# H01R01.net
KiCad netlist of a schematic drawn in EAGLE
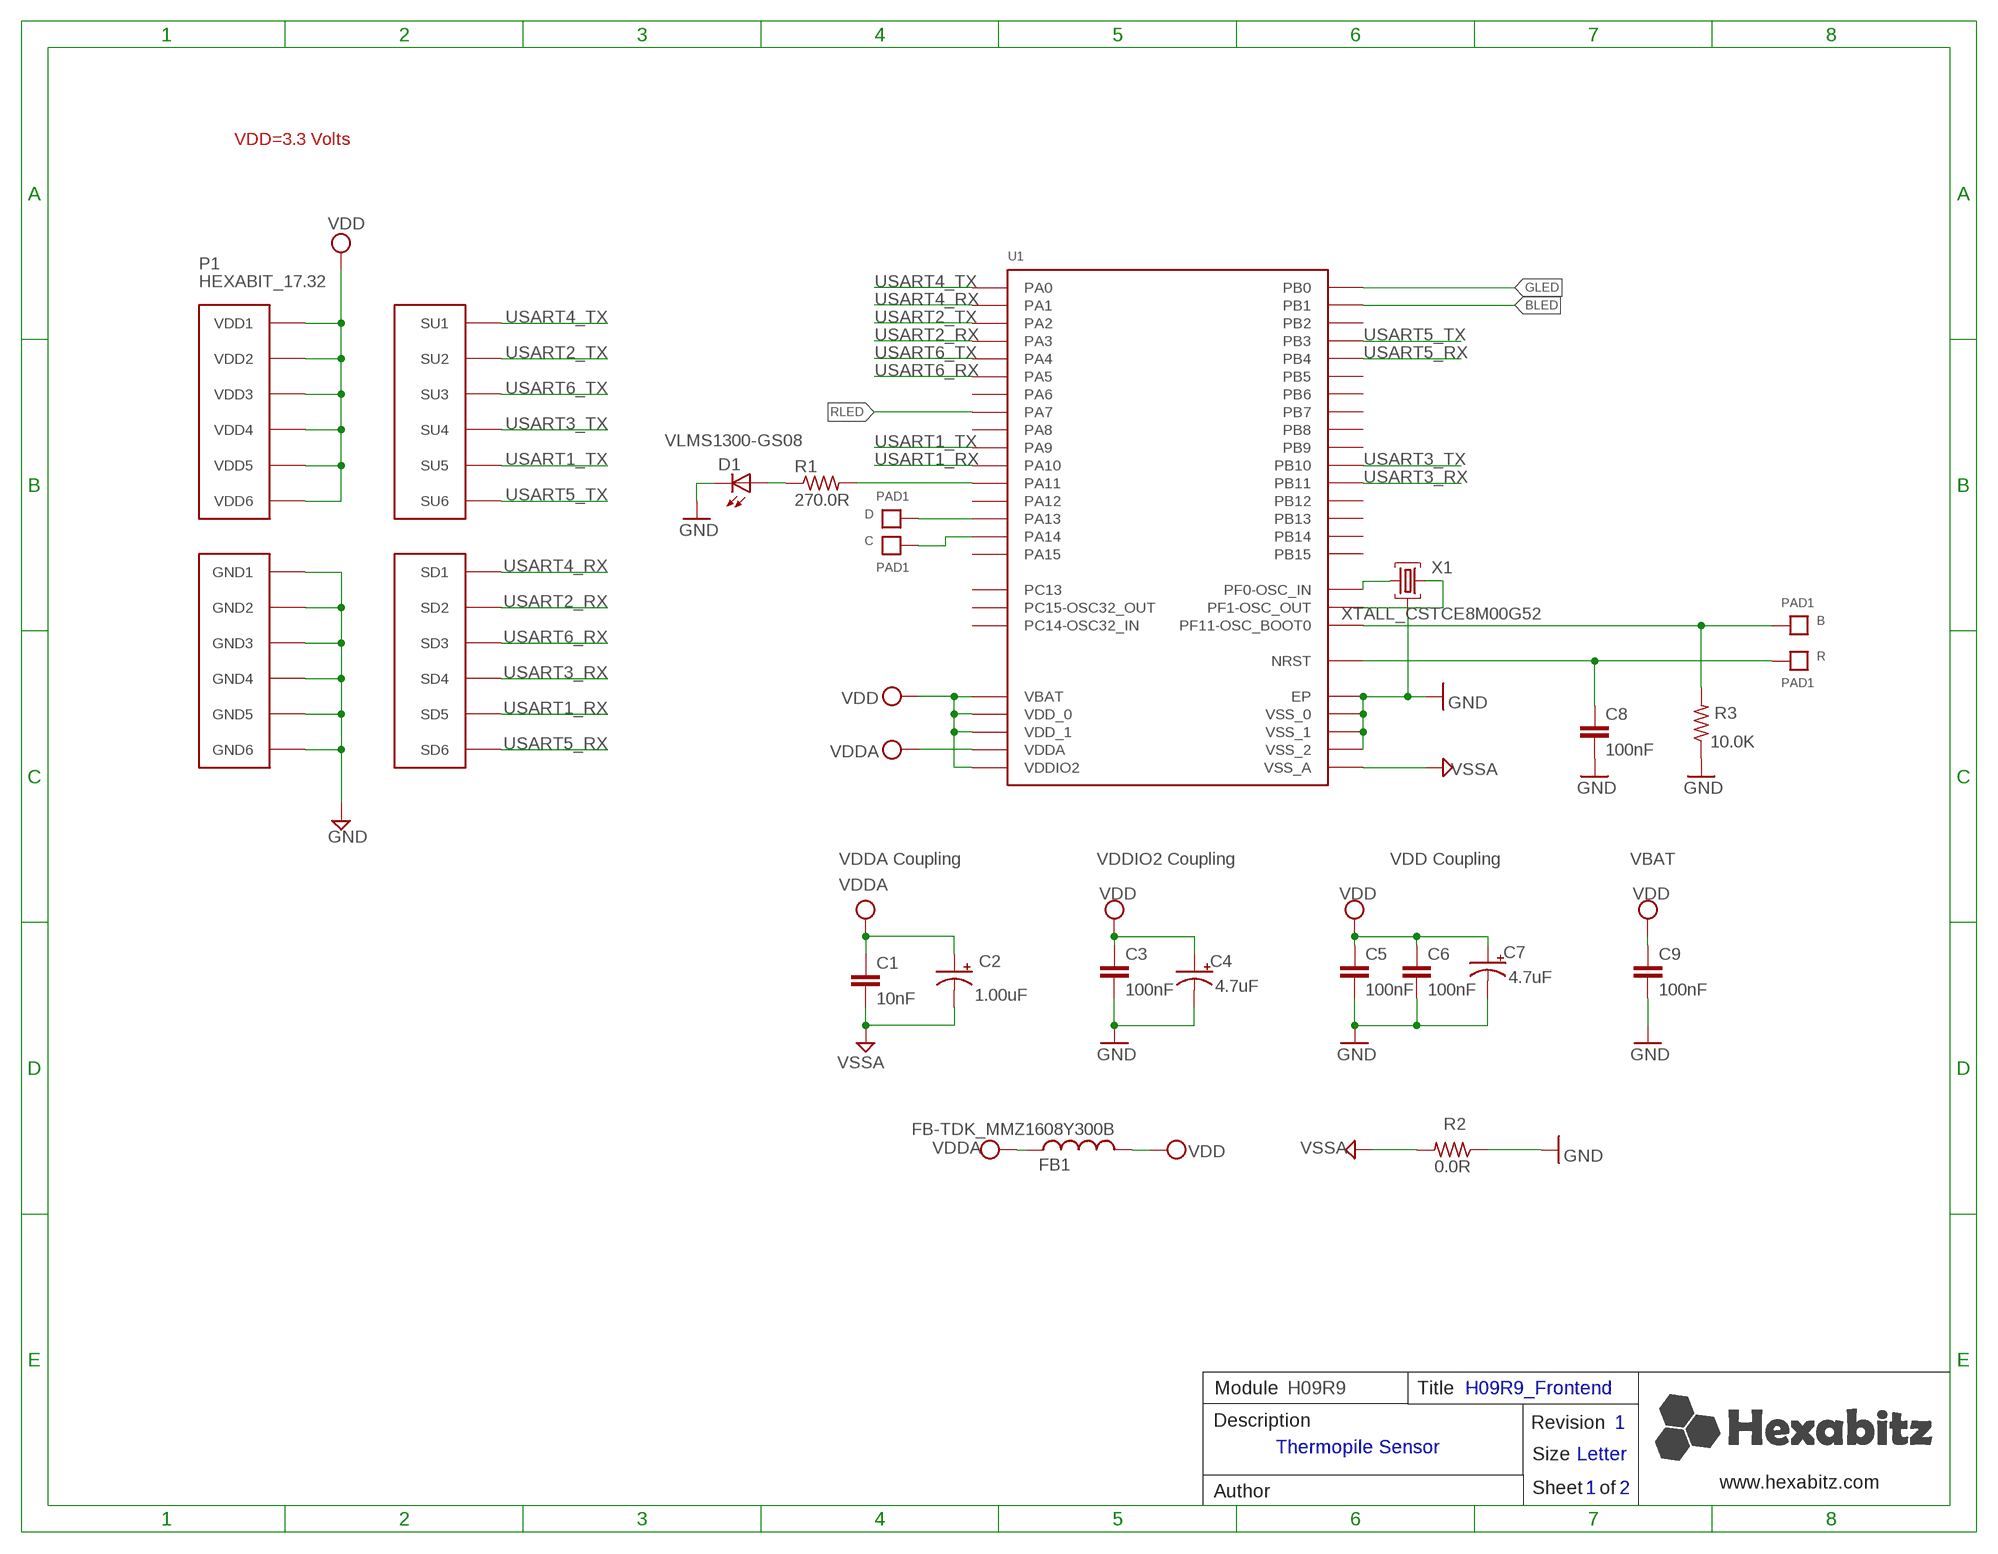
[diagram p0: schematic, sheet 1]
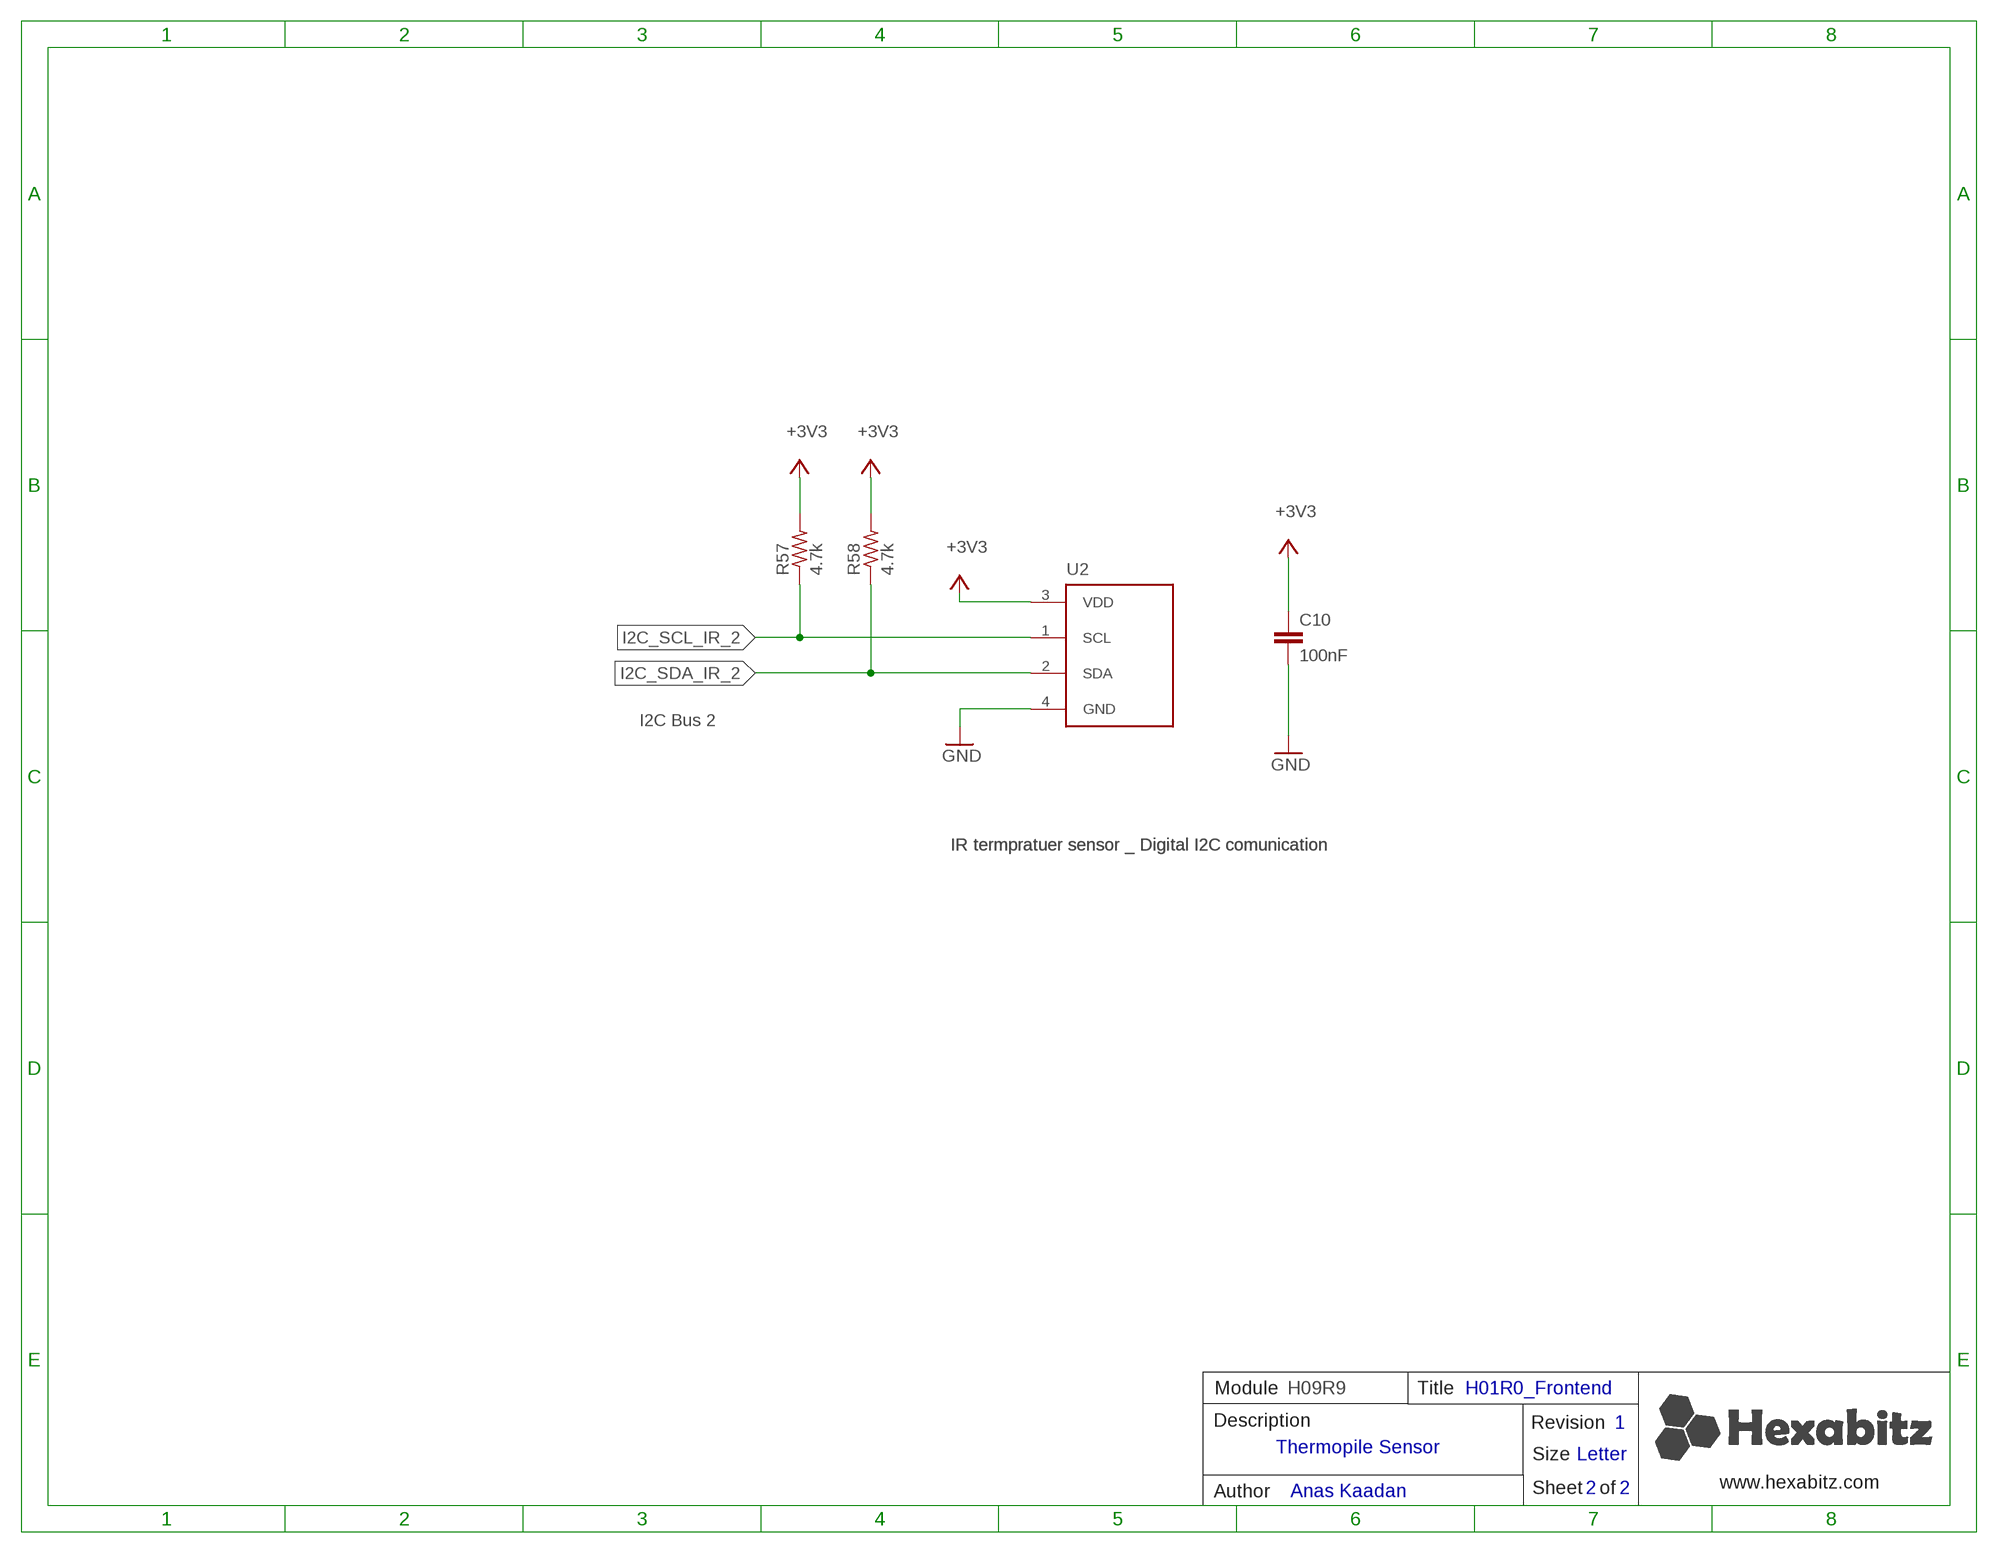
[diagram p1: schematic, sheet 2]

(export (version "E")
  (design (tool "Eeschema 10.0.6"))
  (components
    (comp (ref "C10")
      (value "100nF")
      (footprint "eagle-import:C-0603")
      (fields
        (field (name "CAPACITANCE") "100nF")
        (field (name "MFN") "KEMET")
        (field (name "MPN") "C0603C104K8RACTU")
        (field (name "OCTOPART_URL") "https://octopart.com/c0603c104k8ractu-kemet-145075?r=sp&s=9bS9ASSwSEqMCE9KBEQZ0g")
        (field (name "TOLERANCE") "10%")
        (field (name "VOLTAGE_RATING") "10V")
      )
      (libsource (lib "eagle-import") (part "C-0603"))
    )
    (comp (ref "R57")
      (value "4.7k")
      (footprint "eagle-import:R-0603")
      (fields
        (field (name "MFN") "Yageo")
        (field (name "MPN") "RC0603FR-07270RL")
        (field (name "OCTOPART_URL") "https://octopart.com/crcw06032k20fkea-vishay-40018987")
        (field (name "TOLERANCE") "±1%")
      )
      (libsource (lib "eagle-import") (part "R-0603"))
    )
    (comp (ref "R58")
      (value "4.7k")
      (footprint "eagle-import:R-0603")
      (fields
        (field (name "MFN") "Yageo")
        (field (name "MPN") "RC0603FR-07270RL")
        (field (name "OCTOPART_URL") "https://octopart.com/crcw06032k20fkea-vishay-40018987")
        (field (name "TOLERANCE") "±1%")
      )
      (libsource (lib "eagle-import") (part "R-0603"))
    )
    (comp (ref "U2")
      (value "TSD305-1C55")
      (footprint "eagle-import:TEMPERATURESENSOR-TO5")
      (fields (field (name "MPN") "G-TPMO-101"))
      (libsource (lib "eagle-import") (part "TSD305-1C55"))
    )
    (comp (ref "B")
      (value "PAD1")
      (footprint "eagle-import:PAD1")
      (libsource (lib "eagle-import") (part "PAD1"))
    )
    (comp (ref "C")
      (value "PAD1")
      (footprint "eagle-import:PAD1")
      (libsource (lib "eagle-import") (part "PAD1"))
    )
    (comp (ref "C1")
      (value "10nF")
      (footprint "eagle-import:C-0603")
      (fields
        (field (name "CAPACITANCE") "10nF")
        (field (name "MFN") "KEMET")
        (field (name "MPN") "C0603C103K5RACTU")
        (field (name "OCTOPART_URL") "https://octopart.com/c0603c103k5ractu-kemet-133094?r=sp&s=R_iPBxLnSmGqhkU2rIMFpg")
        (field (name "TOLERANCE") "10%")
        (field (name "VOLTAGE_RATING") "50V")
      )
      (libsource (lib "eagle-import") (part "Hexabitz_C-0603"))
    )
    (comp (ref "C2")
      (value "1.00uF")
      (footprint "eagle-import:C-0805-POL")
      (fields
        (field (name "CAPACITANCE") "1.00uF")
        (field (name "MFN") "Yageo")
        (field (name "MPN") "CC0805KKX7R7BB105")
        (field (name "OCTOPART_URL") "https://octopart.com/cc0805kkx7r7bb105-yageo-8376555?r=sp&s=YKl1wwtkROau_X5nniH2ig")
        (field (name "TOLERANCE") "10%")
        (field (name "VOLTAGE_RATING") "16V")
      )
      (libsource (lib "eagle-import") (part "C-0805-POL"))
    )
    (comp (ref "C3")
      (value "100nF")
      (footprint "eagle-import:C-0603")
      (fields
        (field (name "CAPACITANCE") "100nF")
        (field (name "MFN") "KEMET")
        (field (name "MPN") "C0603C104K8RACTU")
        (field (name "OCTOPART_URL") "https://octopart.com/c0603c104k8ractu-kemet-145075?r=sp&s=9bS9ASSwSEqMCE9KBEQZ0g")
        (field (name "TOLERANCE") "10%")
        (field (name "VOLTAGE_RATING") "10V")
      )
      (libsource (lib "eagle-import") (part "Hexabitz_C-0603"))
    )
    (comp (ref "C4")
      (value "4.7uF")
      (footprint "eagle-import:C-0805-POL")
      (fields
        (field (name "CAPACITANCE") "4.7uF")
        (field (name "MFN") "Murata")
        (field (name "MPN") "GRM21BC81E475KA12L")
        (field (name "OCTOPART_URL") "https://octopart.com/grm21bc81e475ka12l-murata-10331911?r=sp&s=RY3qZSD8T6mG6TC9CHI5qQ")
        (field (name "TOLERANCE") "10%")
        (field (name "VOLTAGE_RATING") "25V")
      )
      (libsource (lib "eagle-import") (part "C-0805-POL"))
    )
    (comp (ref "C5")
      (value "100nF")
      (footprint "eagle-import:C-0603")
      (fields
        (field (name "CAPACITANCE") "100nF")
        (field (name "MFN") "KEMET")
        (field (name "MPN") "C0603C104K8RACTU")
        (field (name "OCTOPART_URL") "https://octopart.com/c0603c104k8ractu-kemet-145075?r=sp&s=9bS9ASSwSEqMCE9KBEQZ0g")
        (field (name "TOLERANCE") "10%")
        (field (name "VOLTAGE_RATING") "10")
      )
      (libsource (lib "eagle-import") (part "Hexabitz_C-0603"))
    )
    (comp (ref "C6")
      (value "100nF")
      (footprint "eagle-import:C-0603")
      (fields
        (field (name "CAPACITANCE") "100nF")
        (field (name "MFN") "KEMET")
        (field (name "MPN") "C0603C104K8RACTU")
        (field (name "OCTOPART_URL") "https://octopart.com/c0603c104k8ractu-kemet-145075?r=sp&s=9bS9ASSwSEqMCE9KBEQZ0g")
        (field (name "TOLERANCE") "10%")
        (field (name "VOLTAGE_RATING") "10V")
      )
      (libsource (lib "eagle-import") (part "Hexabitz_C-0603"))
    )
    (comp (ref "C7")
      (value "4.7uF")
      (footprint "eagle-import:C-0805-POL")
      (fields
        (field (name "CAPACITANCE") "4.7uF")
        (field (name "MFN") "Murata")
        (field (name "MPN") "GRM21BC81E475KA12L")
        (field (name "OCTOPART_URL") "https://octopart.com/grm21bc81e475ka12l-murata-10331911?r=sp&s=RY3qZSD8T6mG6TC9CHI5qQ")
        (field (name "TOLERANCE") "10%")
        (field (name "VOLTAGE_RATING") "25V")
      )
      (libsource (lib "eagle-import") (part "C-0805-POL"))
    )
    (comp (ref "C8")
      (value "100nF")
      (footprint "eagle-import:C-0603")
      (fields
        (field (name "CAPACITANCE") "100nF")
        (field (name "MFN") "KEMET")
        (field (name "MPN") "C0603C104K8RACTU")
        (field (name "OCTOPART_URL") "https://octopart.com/c0603c104k8ractu-kemet-145075?r=sp&s=9bS9ASSwSEqMCE9KBEQZ0g")
        (field (name "TOLERANCE") "10%")
        (field (name "VOLTAGE_RATING") "10V")
      )
      (libsource (lib "eagle-import") (part "Hexabitz_C-0603"))
    )
    (comp (ref "C9")
      (value "100nF")
      (footprint "eagle-import:C-0603")
      (fields
        (field (name "CAPACITANCE") "100nF")
        (field (name "MFN") "KEMET")
        (field (name "MPN") "C0603C104K8RACTU")
        (field (name "OCTOPART_URL") "https://octopart.com/c0603c104k8ractu-kemet-145075?r=sp&s=9bS9ASSwSEqMCE9KBEQZ0g")
        (field (name "TOLERANCE") "10V")
        (field (name "VOLTAGE_RATING") "10%")
      )
      (libsource (lib "eagle-import") (part "Hexabitz_C-0603"))
    )
    (comp (ref "D")
      (value "PAD1")
      (footprint "eagle-import:PAD1")
      (libsource (lib "eagle-import") (part "PAD1"))
    )
    (comp (ref "D1")
      (value "VLMS1300-GS08")
      (footprint "eagle-import:VLMS1300-GS08")
      (fields
        (field (name "MFN") "Vishay")
        (field (name "MPN") "VLMS1300-GS08")
        (field (name "OCTOPART_URL") "https://octopart.com/vlms1300-gs08-vishay-21709201?r=sp&s=_gcP4_q8T1SC6PJQPTQ9yA")
      )
      (libsource (lib "eagle-import") (part "VLMS1300-GS08"))
    )
    (comp (ref "FB1")
      (value "FB-TDK_MMZ1608Y300B")
      (footprint "eagle-import:FB-TDK_MMZ1608Y300B")
      (fields
        (field (name "MFN") "TDK ")
        (field (name "MPN") "MMZ1608Y300B")
        (field (name "OCTOPART_URL") "https://octopart.com/mmz1608y300b-tdk-368280?r=sp&s=cd9_2ZEqQ9q9UNBuQgHAiA")
      )
      (libsource (lib "eagle-import") (part "FB-TDK_MMZ1608Y300B"))
    )
    (comp (ref "P1")
      (value "HEXABIT_17.32")
      (footprint "eagle-import:HEXABIT_17.32")
      (libsource (lib "eagle-import") (part "HEXABIT_?17.32"))
    )
    (comp (ref "R")
      (value "PAD1")
      (footprint "eagle-import:PAD1")
      (libsource (lib "eagle-import") (part "PAD1"))
    )
    (comp (ref "R1")
      (value "270.0R")
      (footprint "eagle-import:R-0603")
      (fields
        (field (name "MFN") "Yageo")
        (field (name "MPN") "RC0603FR-07270RL")
        (field (name "OCTOPART_URL") "https://octopart.com/search?q=RC0603FR-07270RL&start=0")
        (field (name "RESISTANCE") "270.0 Ohm")
        (field (name "TOLERANCE") "5%")
      )
      (libsource (lib "eagle-import") (part "Hexabitz_R-0603"))
    )
    (comp (ref "R2")
      (value "0.0R")
      (footprint "eagle-import:R-0603")
      (fields
        (field (name "MFN") "Yageo")
        (field (name "MPN") "RC0603JR-070RL")
        (field (name "OCTOPART_URL") "https://octopart.com/rc0603jr-070rl-yageo-1241539?r=sp&s=X2NteqRjRNWrnx42Y0aliA")
        (field (name "RESISTANCE") "0.0 Ohm")
      )
      (libsource (lib "eagle-import") (part "Hexabitz_R-0603"))
    )
    (comp (ref "R3")
      (value "10.0K")
      (footprint "eagle-import:R-0603")
      (fields
        (field (name "MFN") "Yageo")
        (field (name "MPN") "RC0603JR-0710KL")
        (field (name "OCTOPART_URL") "https://octopart.com/search?q=RC0603JR-0710KL&start=0")
        (field (name "RESISTANCE") "10.0K Ohm")
        (field (name "TOLERANCE") "5%")
      )
      (libsource (lib "eagle-import") (part "Hexabitz_R-0603"))
    )
    (comp (ref "U1")
      (value "STM32F091CBU6")
      (footprint "eagle-import:STM32F091CBU6")
      (libsource (lib "eagle-import") (part "STM32F091CBU6"))
    )
    (comp (ref "X1")
      (value "XTALL_CSTCE8M00G52")
      (footprint "eagle-import:XTALL_CSTCE8M00G52")
      (fields (field (name "MPN") "CSTCE8M00G52Z-R0"))
      (libsource (lib "eagle-import") (part "XTALL_CSTCE8M00G52"))
    )
  )
  (nets
    (net (code "1") (name "+3V3") (class "Default")
      (node (ref "C10") (pin "1") (pinfunction "1_1") (pintype "passive"))
      (node (ref "R57") (pin "2") (pinfunction "2_2") (pintype "passive"))
      (node (ref "R58") (pin "2") (pinfunction "2_2") (pintype "passive"))
      (node (ref "U2") (pin "3") (pinfunction "VDD_3") (pintype "power_in"))
    )
    (net (code "2") (name "BLED") (class "Default")
      (node (ref "U1") (pin "P$19") (pinfunction "PB1_P$19") (pintype "bidirectional"))
    )
    (net (code "3") (name "GLED") (class "Default")
      (node (ref "U1") (pin "P$18") (pinfunction "PB0_P$18") (pintype "bidirectional"))
    )
    (net (code "4") (name "GND") (class "Default")
      (node (ref "C10") (pin "2") (pinfunction "2_2") (pintype "passive"))
      (node (ref "C3") (pin "2") (pinfunction "2_2") (pintype "passive"))
      (node (ref "C4") (pin "2") (pinfunction "-_2") (pintype "passive"))
      (node (ref "C5") (pin "2") (pinfunction "2_2") (pintype "passive"))
      (node (ref "C6") (pin "2") (pinfunction "2_2") (pintype "passive"))
      (node (ref "C7") (pin "2") (pinfunction "-_2") (pintype "passive"))
      (node (ref "C8") (pin "2") (pinfunction "2_2") (pintype "passive"))
      (node (ref "C9") (pin "2") (pinfunction "2_2") (pintype "passive"))
      (node (ref "D1") (pin "C") (pinfunction "C_C") (pintype "passive"))
      (node (ref "P1") (pin "PAD_PD10") (pinfunction "GND4_PAD_PD10") (pintype "power_in"))
      (node (ref "P1") (pin "PAD_PD11") (pinfunction "GND5_PAD_PD11") (pintype "power_in"))
      (node (ref "P1") (pin "PAD_PD12") (pinfunction "GND6_PAD_PD12") (pintype "power_in"))
      (node (ref "P1") (pin "PAD_PD7") (pinfunction "GND1_PAD_PD7") (pintype "power_in"))
      (node (ref "P1") (pin "PAD_PD8") (pinfunction "GND2_PAD_PD8") (pintype "power_in"))
      (node (ref "P1") (pin "PAD_PD9") (pinfunction "GND3_PAD_PD9") (pintype "power_in"))
      (node (ref "R2") (pin "1") (pinfunction "1_1") (pintype "passive"))
      (node (ref "R3") (pin "1") (pinfunction "1_1") (pintype "passive"))
      (node (ref "U1") (pin "EP") (pinfunction "EP_EP") (pintype "power_in"))
      (node (ref "U1") (pin "P$23") (pinfunction "VSS_0_P$23") (pintype "power_in"))
      (node (ref "U1") (pin "P$35") (pinfunction "VSS_1_P$35") (pintype "power_in"))
      (node (ref "U1") (pin "P$47") (pinfunction "VSS_2_P$47") (pintype "power_in"))
      (node (ref "U2") (pin "4") (pinfunction "GND_4") (pintype "power_in"))
      (node (ref "X1") (pin "P$2") (pinfunction "2_P$2") (pintype "passive"))
    )
    (net (code "5") (name "I2C_SCL_IR_2") (class "Default")
      (node (ref "R57") (pin "1") (pinfunction "1_1") (pintype "passive"))
      (node (ref "U2") (pin "1") (pinfunction "SCL_1") (pintype "bidirectional"))
    )
    (net (code "6") (name "I2C_SDA_IR_2") (class "Default")
      (node (ref "R58") (pin "1") (pinfunction "1_1") (pintype "passive"))
      (node (ref "U2") (pin "2") (pinfunction "SDA_2") (pintype "bidirectional"))
    )
    (net (code "7") (name "Net-(D1-PadA)") (class "Default")
      (node (ref "D1") (pin "A") (pinfunction "A_A") (pintype "passive"))
      (node (ref "R1") (pin "1") (pinfunction "1_1") (pintype "passive"))
    )
    (net (code "8") (name "Net-(U1-NRST)") (class "Default")
      (node (ref "C8") (pin "1") (pinfunction "1_1") (pintype "passive"))
      (node (ref "R") (pin "P$1") (pinfunction "P$1_P$1") (pintype "passive"))
      (node (ref "R") (pin "P$2") (pinfunction "P$1_P$2") (pintype "passive"))
      (node (ref "U1") (pin "P$7") (pinfunction "NRST_P$7") (pintype "passive"))
    )
    (net (code "9") (name "Net-(U1-PA11)") (class "Default")
      (node (ref "R1") (pin "2") (pinfunction "2_2") (pintype "passive"))
      (node (ref "U1") (pin "P$32") (pinfunction "PA11_P$32") (pintype "bidirectional"))
    )
    (net (code "10") (name "Net-(U1-PA13)") (class "Default")
      (node (ref "D") (pin "P$1") (pinfunction "P$1_P$1") (pintype "passive"))
      (node (ref "D") (pin "P$2") (pinfunction "P$1_P$2") (pintype "passive"))
      (node (ref "U1") (pin "P$34") (pinfunction "PA13_P$34") (pintype "bidirectional"))
    )
    (net (code "11") (name "Net-(U1-PA14)") (class "Default")
      (node (ref "C") (pin "P$1") (pinfunction "P$1_P$1") (pintype "passive"))
      (node (ref "C") (pin "P$2") (pinfunction "P$1_P$2") (pintype "passive"))
      (node (ref "U1") (pin "P$37") (pinfunction "PA14_P$37") (pintype "bidirectional"))
    )
    (net (code "12") (name "Net-(U1-PF0-OSC_IN)") (class "Default")
      (node (ref "U1") (pin "P$5") (pinfunction "PF0-OSC_IN_P$5") (pintype "bidirectional"))
      (node (ref "X1") (pin "P$1") (pinfunction "1_P$1") (pintype "passive"))
    )
    (net (code "13") (name "Net-(U1-PF1-OSC_OUT)") (class "Default")
      (node (ref "U1") (pin "P$6") (pinfunction "PF1-OSC_OUT_P$6") (pintype "bidirectional"))
      (node (ref "X1") (pin "P$3") (pinfunction "3_P$3") (pintype "passive"))
    )
    (net (code "14") (name "Net-(U1-PF11-OSC_BOOT0)") (class "Default")
      (node (ref "B") (pin "P$1") (pinfunction "P$1_P$1") (pintype "passive"))
      (node (ref "B") (pin "P$2") (pinfunction "P$1_P$2") (pintype "passive"))
      (node (ref "R3") (pin "2") (pinfunction "2_2") (pintype "passive"))
      (node (ref "U1") (pin "P$44") (pinfunction "PF11-OSC_BOOT0_P$44") (pintype "bidirectional"))
    )
    (net (code "15") (name "RLED") (class "Default")
      (node (ref "U1") (pin "P$17") (pinfunction "PA7_P$17") (pintype "bidirectional"))
    )
    (net (code "16") (name "USART1_RX") (class "Default")
      (node (ref "P1") (pin "PAD_PD5") (pinfunction "SD5_PAD_PD5") (pintype "bidirectional"))
      (node (ref "U1") (pin "P$31") (pinfunction "PA10_P$31") (pintype "bidirectional"))
    )
    (net (code "17") (name "USART1_TX") (class "Default")
      (node (ref "P1") (pin "PAD_PU5") (pinfunction "SU5_PAD_PU5") (pintype "bidirectional"))
      (node (ref "U1") (pin "P$30") (pinfunction "PA9_P$30") (pintype "bidirectional"))
    )
    (net (code "18") (name "USART2_RX") (class "Default")
      (node (ref "P1") (pin "PAD_PD2") (pinfunction "SD2_PAD_PD2") (pintype "bidirectional"))
      (node (ref "U1") (pin "P$13") (pinfunction "PA3_P$13") (pintype "bidirectional"))
    )
    (net (code "19") (name "USART2_TX") (class "Default")
      (node (ref "P1") (pin "PAD_PU2") (pinfunction "SU2_PAD_PU2") (pintype "bidirectional"))
      (node (ref "U1") (pin "P$12") (pinfunction "PA2_P$12") (pintype "bidirectional"))
    )
    (net (code "20") (name "USART3_RX") (class "Default")
      (node (ref "P1") (pin "PAD_PD4") (pinfunction "SD4_PAD_PD4") (pintype "bidirectional"))
      (node (ref "U1") (pin "P$22") (pinfunction "PB11_P$22") (pintype "bidirectional"))
    )
    (net (code "21") (name "USART3_TX") (class "Default")
      (node (ref "P1") (pin "PAD_PU4") (pinfunction "SU4_PAD_PU4") (pintype "bidirectional"))
      (node (ref "U1") (pin "P$21") (pinfunction "PB10_P$21") (pintype "bidirectional"))
    )
    (net (code "22") (name "USART4_RX") (class "Default")
      (node (ref "P1") (pin "PAD_PD1") (pinfunction "SD1_PAD_PD1") (pintype "bidirectional"))
      (node (ref "U1") (pin "P$11") (pinfunction "PA1_P$11") (pintype "bidirectional"))
    )
    (net (code "23") (name "USART4_TX") (class "Default")
      (node (ref "P1") (pin "PAD_PU1") (pinfunction "SU1_PAD_PU1") (pintype "bidirectional"))
      (node (ref "U1") (pin "P$10") (pinfunction "PA0_P$10") (pintype "bidirectional"))
    )
    (net (code "24") (name "USART5_RX") (class "Default")
      (node (ref "P1") (pin "PAD_PD6") (pinfunction "SD6_PAD_PD6") (pintype "bidirectional"))
      (node (ref "U1") (pin "P$40") (pinfunction "PB4_P$40") (pintype "bidirectional"))
    )
    (net (code "25") (name "USART5_TX") (class "Default")
      (node (ref "P1") (pin "PAD_PU6") (pinfunction "SU6_PAD_PU6") (pintype "bidirectional"))
      (node (ref "U1") (pin "P$39") (pinfunction "PB3_P$39") (pintype "bidirectional"))
    )
    (net (code "26") (name "USART6_RX") (class "Default")
      (node (ref "P1") (pin "PAD_PD3") (pinfunction "SD3_PAD_PD3") (pintype "bidirectional"))
      (node (ref "U1") (pin "P$15") (pinfunction "PA5_P$15") (pintype "bidirectional"))
    )
    (net (code "27") (name "USART6_TX") (class "Default")
      (node (ref "P1") (pin "PAD_PU3") (pinfunction "SU3_PAD_PU3") (pintype "bidirectional"))
      (node (ref "U1") (pin "P$14") (pinfunction "PA4_P$14") (pintype "bidirectional"))
    )
    (net (code "28") (name "VDD") (class "Default")
      (node (ref "C3") (pin "1") (pinfunction "1_1") (pintype "passive"))
      (node (ref "C4") (pin "1") (pinfunction "+_1") (pintype "passive"))
      (node (ref "C5") (pin "1") (pinfunction "1_1") (pintype "passive"))
      (node (ref "C6") (pin "1") (pinfunction "1_1") (pintype "passive"))
      (node (ref "C7") (pin "1") (pinfunction "+_1") (pintype "passive"))
      (node (ref "C9") (pin "1") (pinfunction "1_1") (pintype "passive"))
      (node (ref "FB1") (pin "2") (pinfunction "2_2") (pintype "passive"))
      (node (ref "P1") (pin "PAD_PU10") (pinfunction "VDD4_PAD_PU10") (pintype "power_in"))
      (node (ref "P1") (pin "PAD_PU11") (pinfunction "VDD5_PAD_PU11") (pintype "power_in"))
      (node (ref "P1") (pin "PAD_PU12") (pinfunction "VDD6_PAD_PU12") (pintype "power_in"))
      (node (ref "P1") (pin "PAD_PU7") (pinfunction "VDD1_PAD_PU7") (pintype "power_in"))
      (node (ref "P1") (pin "PAD_PU8") (pinfunction "VDD2_PAD_PU8") (pintype "power_in"))
      (node (ref "P1") (pin "PAD_PU9") (pinfunction "VDD3_PAD_PU9") (pintype "power_in"))
      (node (ref "U1") (pin "P$1") (pinfunction "VBAT_P$1") (pintype "power_in"))
      (node (ref "U1") (pin "P$24") (pinfunction "VDD_0_P$24") (pintype "power_in"))
      (node (ref "U1") (pin "P$36") (pinfunction "VDDIO2_P$36") (pintype "power_in"))
      (node (ref "U1") (pin "P$48") (pinfunction "VDD_1_P$48") (pintype "power_in"))
    )
    (net (code "29") (name "VDDA") (class "Default")
      (node (ref "C1") (pin "1") (pinfunction "1_1") (pintype "passive"))
      (node (ref "C2") (pin "1") (pinfunction "+_1") (pintype "passive"))
      (node (ref "FB1") (pin "1") (pinfunction "1_1") (pintype "passive"))
      (node (ref "U1") (pin "P$9") (pinfunction "VDDA_P$9") (pintype "power_in"))
    )
    (net (code "30") (name "VSSA") (class "Default")
      (node (ref "C1") (pin "2") (pinfunction "2_2") (pintype "passive"))
      (node (ref "C2") (pin "2") (pinfunction "-_2") (pintype "passive"))
      (node (ref "R2") (pin "2") (pinfunction "2_2") (pintype "passive"))
      (node (ref "U1") (pin "P$8") (pinfunction "VSS_A_P$8") (pintype "power_in"))
    )
    (net (code "31") (name "unconnected-(U1-PA6-PadP$16)") (class "Default")
      (node (ref "U1") (pin "P$16") (pinfunction "PA6_P$16") (pintype "bidirectional"))
    )
    (net (code "32") (name "unconnected-(U1-PA8-PadP$29)") (class "Default")
      (node (ref "U1") (pin "P$29") (pinfunction "PA8_P$29") (pintype "bidirectional"))
    )
    (net (code "33") (name "unconnected-(U1-PA12-PadP$33)") (class "Default")
      (node (ref "U1") (pin "P$33") (pinfunction "PA12_P$33") (pintype "bidirectional"))
    )
    (net (code "34") (name "unconnected-(U1-PA15-PadP$38)") (class "Default")
      (node (ref "U1") (pin "P$38") (pinfunction "PA15_P$38") (pintype "bidirectional"))
    )
    (net (code "35") (name "unconnected-(U1-PB2-PadP$20)") (class "Default")
      (node (ref "U1") (pin "P$20") (pinfunction "PB2_P$20") (pintype "bidirectional"))
    )
    (net (code "36") (name "unconnected-(U1-PB5-PadP$41)") (class "Default")
      (node (ref "U1") (pin "P$41") (pinfunction "PB5_P$41") (pintype "bidirectional"))
    )
    (net (code "37") (name "unconnected-(U1-PB6-PadP$42)") (class "Default")
      (node (ref "U1") (pin "P$42") (pinfunction "PB6_P$42") (pintype "bidirectional"))
    )
    (net (code "38") (name "unconnected-(U1-PB7-PadP$43)") (class "Default")
      (node (ref "U1") (pin "P$43") (pinfunction "PB7_P$43") (pintype "bidirectional"))
    )
    (net (code "39") (name "unconnected-(U1-PB8-PadP$45)") (class "Default")
      (node (ref "U1") (pin "P$45") (pinfunction "PB8_P$45") (pintype "bidirectional"))
    )
    (net (code "40") (name "unconnected-(U1-PB9-PadP$46)") (class "Default")
      (node (ref "U1") (pin "P$46") (pinfunction "PB9_P$46") (pintype "bidirectional"))
    )
    (net (code "41") (name "unconnected-(U1-PB12-PadP$25)") (class "Default")
      (node (ref "U1") (pin "P$25") (pinfunction "PB12_P$25") (pintype "bidirectional"))
    )
    (net (code "42") (name "unconnected-(U1-PB13-PadP$26)") (class "Default")
      (node (ref "U1") (pin "P$26") (pinfunction "PB13_P$26") (pintype "bidirectional"))
    )
    (net (code "43") (name "unconnected-(U1-PB14-PadP$27)") (class "Default")
      (node (ref "U1") (pin "P$27") (pinfunction "PB14_P$27") (pintype "bidirectional"))
    )
    (net (code "44") (name "unconnected-(U1-PB15-PadP$28)") (class "Default")
      (node (ref "U1") (pin "P$28") (pinfunction "PB15_P$28") (pintype "bidirectional"))
    )
    (net (code "45") (name "unconnected-(U1-PC13-PadP$2)") (class "Default")
      (node (ref "U1") (pin "P$2") (pinfunction "PC13_P$2") (pintype "bidirectional"))
    )
    (net (code "46") (name "unconnected-(U1-PC14-OSC32_IN-PadP$3)") (class "Default")
      (node (ref "U1") (pin "P$3") (pinfunction "PC14-OSC32_IN_P$3") (pintype "bidirectional"))
    )
    (net (code "47") (name "unconnected-(U1-PC15-OSC32_OUT-PadP$4)") (class "Default")
      (node (ref "U1") (pin "P$4") (pinfunction "PC15-OSC32_OUT_P$4") (pintype "bidirectional"))
    )
  )
)
